# Hall_Touch.net
KiCad netlist of a schematic drawn in EAGLE
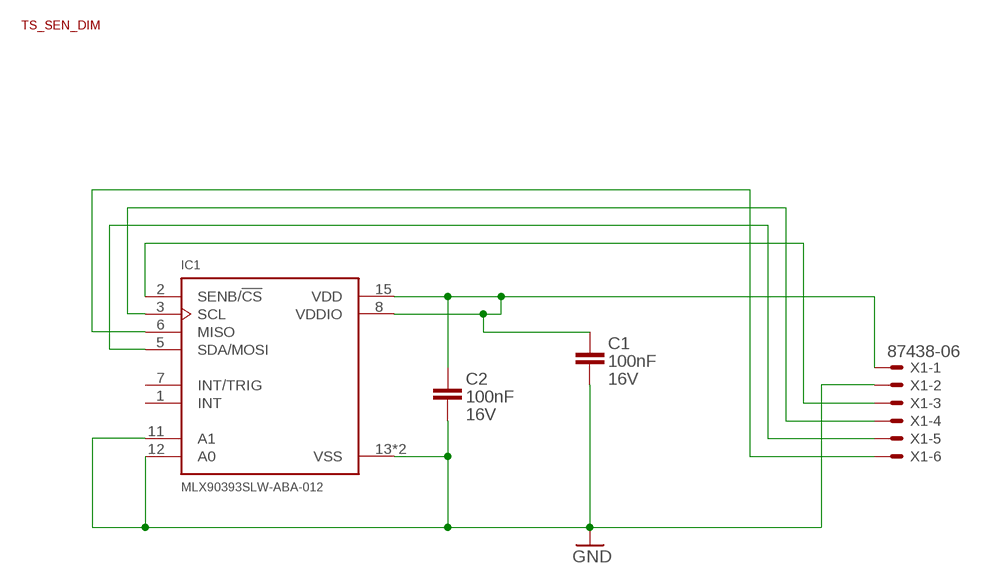
[diagram p0: schematic, sheet 1]

(export (version "E")
  (design (tool "Eeschema 10.0.6"))
  (components
    (comp (ref "C1")
      (value "GCM155R71C104JA55")
      (footprint "eagle-import:C0402")
      (fields
        (field (name "CAPACITANCE") "100nF")
        (field (name "TOLERANCE") "±5%")
        (field (name "VOLTAGE") "16V")
      )
      (libsource (lib "eagle-import") (part "GCM?R71551C104JA55"))
    )
    (comp (ref "C2")
      (value "GCM155R71C104JA55")
      (footprint "eagle-import:C0402")
      (fields
        (field (name "CAPACITANCE") "100nF")
        (field (name "TOLERANCE") "±5%")
        (field (name "VOLTAGE") "16V")
      )
      (libsource (lib "eagle-import") (part "GCM?R71551C104JA55"))
    )
    (comp (ref "DIMENSION1")
      (value "TS_SEN_DIM")
      (footprint "eagle-import:SEN_DIM")
      (libsource (lib "eagle-import") (part "TS_SEN_DIM"))
    )
    (comp (ref "IC1")
      (value "MLX90393SLW-ABA-012")
      (footprint "eagle-import:QFN50P300X300X100-17T180N")
      (libsource (lib "eagle-import") (part "MLX90393?-SLWABA-012"))
    )
    (comp (ref "X1")
      (value "87438-06")
      (footprint "eagle-import:87438-06")
      (fields (field (name "MF") "MOLEX") (field (name "MPN") "87438-0643"))
      (libsource (lib "eagle-import") (part "87438-06"))
    )
  )
  (nets
    (net (code "1") (name "GND") (class "Default")
      (node (ref "C1") (pin "2") (pinfunction "2_2") (pintype "passive"))
      (node (ref "C2") (pin "2") (pinfunction "2_2") (pintype "passive"))
      (node (ref "IC1") (pin "11") (pinfunction "A1_11") (pintype "input"))
      (node (ref "IC1") (pin "12") (pinfunction "A0_12") (pintype "input"))
      (node (ref "IC1") (pin "13") (pinfunction "VSS_13") (pintype "power_in"))
      (node (ref "IC1") (pin "17") (pinfunction "VSS_17") (pintype "power_in"))
      (node (ref "X1") (pin "2") (pinfunction "S_2") (pintype "passive"))
    )
    (net (code "2") (name "Net-(IC1-MISO)") (class "Default")
      (node (ref "IC1") (pin "6") (pinfunction "MISO_6") (pintype "output"))
      (node (ref "X1") (pin "6") (pinfunction "S_6") (pintype "passive"))
    )
    (net (code "3") (name "Net-(IC1-SCL)") (class "Default")
      (node (ref "IC1") (pin "3") (pinfunction "SCL_3") (pintype "input"))
      (node (ref "X1") (pin "4") (pinfunction "S_4") (pintype "passive"))
    )
    (net (code "4") (name "Net-(IC1-SDA{slash}MOSI)") (class "Default")
      (node (ref "IC1") (pin "5") (pinfunction "SDA/MOSI_5") (pintype "bidirectional"))
      (node (ref "X1") (pin "5") (pinfunction "S_5") (pintype "passive"))
    )
    (net (code "5") (name "Net-(IC1-SENB{slash}~{CS})") (class "Default")
      (node (ref "IC1") (pin "2") (pinfunction "SENB/~{CS}_2") (pintype "input"))
      (node (ref "X1") (pin "3") (pinfunction "S_3") (pintype "passive"))
    )
    (net (code "6") (name "Net-(IC1-VDD)") (class "Default")
      (node (ref "C1") (pin "1") (pinfunction "1_1") (pintype "passive"))
      (node (ref "C2") (pin "1") (pinfunction "1_1") (pintype "passive"))
      (node (ref "IC1") (pin "15") (pinfunction "VDD_15") (pintype "power_in"))
      (node (ref "IC1") (pin "8") (pinfunction "VDDIO_8") (pintype "power_in"))
      (node (ref "X1") (pin "1") (pinfunction "S_1") (pintype "passive"))
    )
    (net (code "7") (name "unconnected-(IC1-INT-Pad1)") (class "Default")
      (node (ref "IC1") (pin "1") (pinfunction "INT_1") (pintype "output"))
    )
    (net (code "8") (name "unconnected-(IC1-INT{slash}TRIG-Pad7)") (class "Default")
      (node (ref "IC1") (pin "7") (pinfunction "INT/TRIG_7") (pintype "bidirectional"))
    )
  )
)
